# LED_example.net
KiCad netlist of a schematic drawn in Altium Designer
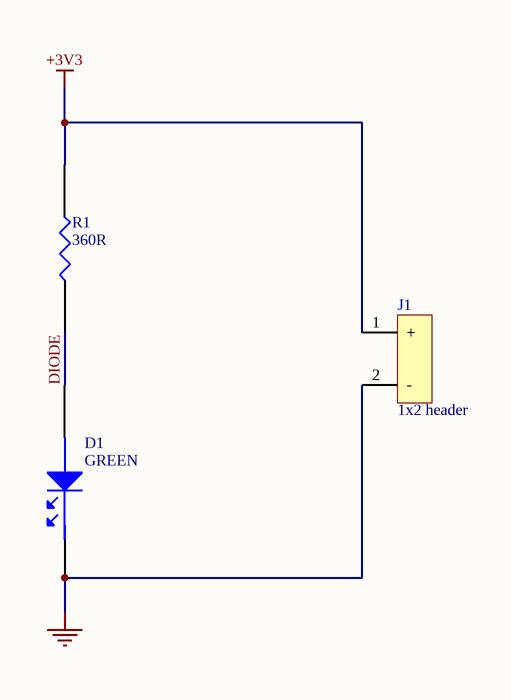
[diagram p0: LED_example.SchDoc]

(export (version "E")
  (design (tool "Eeschema 10.0.6"))
  (components
    (comp (ref "D1")
      (value "GREEN")
      (footprint "LED0603G")
      (description "LED GREEN 0603 SMD")
      (fields
        (field (name "MANUFACTURER") "Panasonic SSG")
        (field (name "MANUFACTURER PART NUMBER") "LNJ337W83RA")
      )
      (libsource (lib "LED_Schlib") (part "LNJ337W83RA"))
    )
    (comp (ref "J1")
      (value "1x2 header")
      (footprint "Header 1x2")
      (description "KK 254 Wire-to-Board Header, Vertical, with Friction Lock, 2 Circuits, Gold (Au) Plating")
      (fields (field (name "MANUFACTURER") "Molex") (field (name "MANUFACTURER PART NUMBER") "22-29-2021"))
      (libsource (lib "LED_Schlib") (part "22-29-2021"))
    )
    (comp (ref "R1")
      (value "360R")
      (footprint "R0805")
      (description "Res Thick Film 0805 360 Ohm 1% 1/8W ±100ppm/°C Molded SMD SMD Paper T/R")
      (fields
        (field (name "MANUFACTURER") "Vishay")
        (field (name "MANUFACTURER PART NUMBER") "CRCW0805360RFKEA")
      )
      (libsource (lib "LED_Schlib") (part "CRCW0805360RFKEA"))
    )
  )
  (nets
    (net (code "1") (name "+3V3") (class "Default")
      (node (ref "J1") (pin "1") (pinfunction "+_1") (pintype "passive"))
      (node (ref "R1") (pin "2") (pinfunction "2_2") (pintype "passive"))
    )
    (net (code "2") (name "/DIODE") (class "Default")
      (node (ref "D1") (pin "2") (pinfunction "2_2") (pintype "passive"))
      (node (ref "R1") (pin "1") (pinfunction "1_1") (pintype "passive"))
    )
    (net (code "3") (name "GND") (class "Default")
      (node (ref "D1") (pin "1") (pinfunction "1_1") (pintype "passive"))
      (node (ref "J1") (pin "2") (pinfunction "-_2") (pintype "passive"))
    )
  )
)
